# DC-DC_VCC_IN__3V.net
KiCad netlist of a schematic drawn in Altium Designer
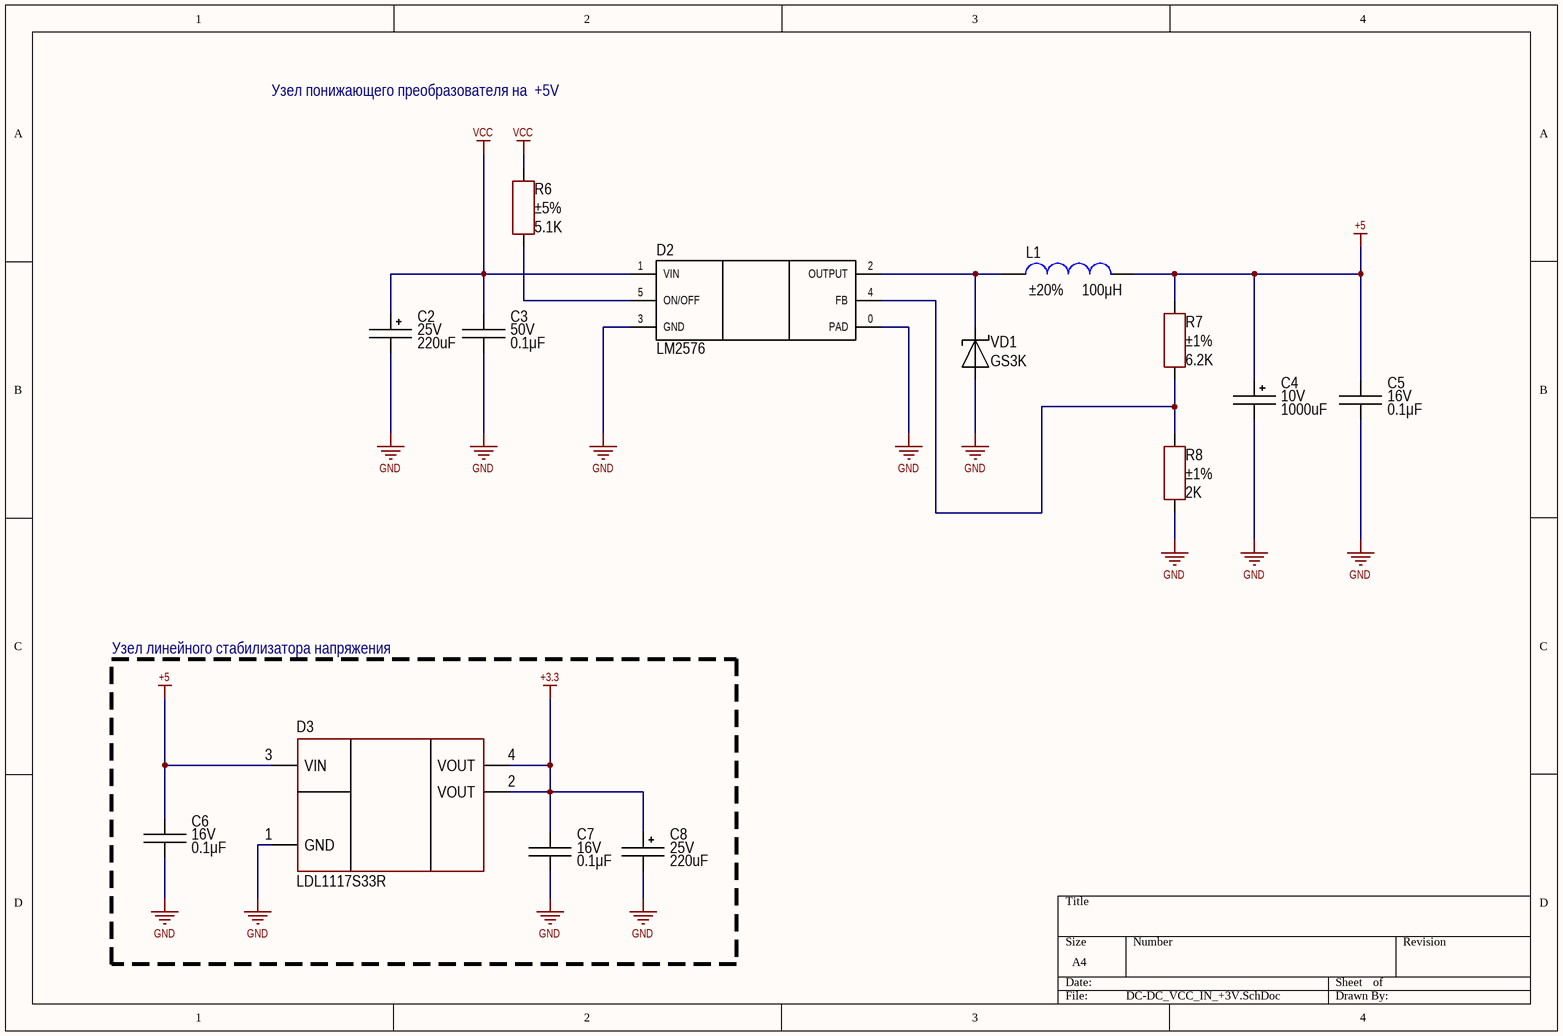
[diagram p0: DC-DC_VCC_IN_+3V.SchDoc]

(export (version "E")
  (design (tool "Eeschema 10.0.6"))
  (components
    (comp (ref "C2")
      (value "220uF")
      (footprint "CAP: D6.3C2.5H11")
      (fields
        (field (name "MANUFACTURER") "Aishi")
        (field (name "PARTNUMBER") "42330")
        (field (name "VALUEMANUFACTURERPARTNUMBER") "Aluminium capacitor, 220uF, 25V, ±20%, 54mOhm, 6.3x12, -55...+105°C")
        (field (name "VOLTAGE") "25V")
      )
      (libsource (lib "capacitor") (part "Aluminium"))
    )
    (comp (ref "C3")
      (value "0.1μF")
      (footprint "CAP: 0603")
      (fields
        (field (name "MANUFACTURER") "Yageo")
        (field (name "PARTNUMBER") "CC0603KRX7R7BB104")
        (field (name "VALUEMANUFACTURERPARTNUMBER") "Ceramic capacitor, 0.1μF, X7R, ±10%, 50V, 0603, -55...+125°C")
        (field (name "VOLTAGE") "50V")
      )
      (libsource (lib "capacitor") (part "Ceramic_0603"))
    )
    (comp (ref "C4")
      (value "1000uF")
      (footprint "CAP: D8C3.5H12")
      (fields
        (field (name "MANUFACTURER") "Aishi")
        (field (name "PARTNUMBER") "01675")
        (field (name "VALUEMANUFACTURERPARTNUMBER") "Aluminium capacitor, 1000uF, 10V, ±20%, 54mOhm, 8x12, -55...+105°C")
        (field (name "VOLTAGE") "10V")
      )
      (libsource (lib "capacitor") (part "Aluminium"))
    )
    (comp (ref "C5")
      (value "0.1μF")
      (footprint "CAP: 0603")
      (fields
        (field (name "MANUFACTURER") "Yageo")
        (field (name "PARTNUMBER") "CC0603KRX7R7BB104")
        (field (name "VALUEMANUFACTURERPARTNUMBER") "Ceramic capacitor, 0.1μF, X7R, ±10%, 16V, 0603, -55...+125°C")
        (field (name "VOLTAGE") "16V")
      )
      (libsource (lib "capacitor") (part "Ceramic_0603"))
    )
    (comp (ref "C6")
      (value "0.1μF")
      (footprint "CAP: 0603")
      (fields
        (field (name "MANUFACTURER") "Yageo")
        (field (name "PARTNUMBER") "CC0603KRX7R7BB104")
        (field (name "VALUEMANUFACTURERPARTNUMBER") "Ceramic capacitor, 0.1μF, X7R, ±10%, 16V, 0603, -55...+125°C")
        (field (name "VOLTAGE") "16V")
      )
      (libsource (lib "capacitor") (part "Ceramic_0603"))
    )
    (comp (ref "C7")
      (value "0.1μF")
      (footprint "CAP: 0603")
      (fields
        (field (name "MANUFACTURER") "Yageo")
        (field (name "PARTNUMBER") "CC0603KRX7R7BB104")
        (field (name "VALUEMANUFACTURERPARTNUMBER") "Ceramic capacitor, 0.1μF, X7R, ±10%, 16V, 0603, -55...+125°C")
        (field (name "VOLTAGE") "16V")
      )
      (libsource (lib "capacitor") (part "Ceramic_0603"))
    )
    (comp (ref "C8")
      (value "220uF")
      (footprint "CAP: D6.3C2.5H11")
      (fields
        (field (name "MANUFACTURER") "Aishi")
        (field (name "PARTNUMBER") "42330")
        (field (name "VALUEMANUFACTURERPARTNUMBER") "Aluminium capacitor, 220uF, 25V, ±20%, 54mOhm, 6.3x12, -55...+105°C")
        (field (name "VOLTAGE") "25V")
      )
      (libsource (lib "capacitor") (part "Aluminium"))
    )
    (comp (ref "D2")
      (value "~")
      (footprint "TO-220-5")
      (description "Step-Down Voltage Regulator")
      (fields
        (field (name "MANUFACTURER") "texas instruments")
        (field (name "VALUEMANUFACTURERPARTNUMBER") "Step-Down Voltage Regulator, 7-40V, 52kHz, 1.23V to 37V, 3A, -40...+125°C, TO-220")
        (field (name "PARTNUMBER") "LM2576")
      )
      (libsource (lib "ic-power-supply") (part "LM2576"))
    )
    (comp (ref "D3")
      (value "~")
      (footprint "SOT223")
      (description "Linear voltage regulator")
      (fields
        (field (name "MANUFACTURER") "STMicroelectronics")
        (field (name "VALUEMANUFACTURERPARTNUMBER") "Linear voltage regulator, input 3.9...18V, 0.6V, output 3.3V, 1.2A, -40...+85°C, SOT223")
        (field (name "PARTNUMBER") "LDL1117S33R")
      )
      (libsource (lib "ic-power-supply") (part "LDL1117S33R"))
    )
    (comp (ref "L1")
      (value "100μH")
      (footprint "CDRH")
      (fields
        (field (name "MANUFACTURER") "Bourns")
        (field (name "PARTNUMBER") "CDRH")
        (field (name "VALUEMANUFACTURERPARTNUMBER") "Fixed inductor, 100μH, ±20%, CDRH101R, 3A, -40...+150°C")
        (field (name "TOLERANCE") "±20%")
      )
      (libsource (lib "inductor") (part "Inductor_CDRH"))
    )
    (comp (ref "R6")
      (value "5.1K")
      (footprint "RES: 0603")
      (fields
        (field (name "MANUFACTURER") "Yageo")
        (field (name "PARTNUMBER") "RC0603JR-07100RL")
        (field (name "VALUEMANUFACTURERPARTNUMBER") "Resistor film, 5.1K, ±5%, 0603, 0.1W, -55...+125°C")
        (field (name "TOLERANCE") "±5%")
      )
      (libsource (lib "resistor") (part "Resistor_0603"))
    )
    (comp (ref "R7")
      (value "6.2K")
      (footprint "RES: 0603")
      (fields
        (field (name "MANUFACTURER") "Yageo")
        (field (name "PARTNUMBER") "RC0603JR-07100RL")
        (field (name "VALUEMANUFACTURERPARTNUMBER") "Resistor film, 6.2K, ±1%, 0603, 0.1W, -55...+125°C")
        (field (name "TOLERANCE") "±1%")
      )
      (libsource (lib "resistor") (part "Resistor_0603"))
    )
    (comp (ref "R8")
      (value "2K")
      (footprint "RES: 0603")
      (fields
        (field (name "MANUFACTURER") "Yageo")
        (field (name "PARTNUMBER") "RC0603JR-07100RL")
        (field (name "VALUEMANUFACTURERPARTNUMBER") "Resistor film, 2K, ±1%, 0603, 0.1W, -55...+125°C")
        (field (name "TOLERANCE") "±1%")
      )
      (libsource (lib "resistor") (part "Resistor_0603"))
    )
    (comp (ref "VD1")
      (value "~")
      (footprint "DIODE: SMC")
      (fields
        (field (name "MANUFACTURER") "Yangzhou Yangjie Electronic Technology Co., Ltd.")
        (field (name "VALUEMANUFACTURERPARTNUMBER") "Schottky diode, 800V, 3A, 1.15V, 15pF, DO-214AB / SMC, -55...+150°C")
        (field (name "VOLTAGE") "800V")
        (field (name "PARTNUMBER") "GS3K")
      )
      (libsource (lib "diode") (part "Schottky_single"))
    )
  )
  (nets
    (net (code "1") (name "+3.3") (class "Default")
      (node (ref "C7") (pin "2") (pinfunction "2_2") (pintype "passive"))
      (node (ref "C8") (pin "1") (pinfunction "1_1") (pintype "passive"))
      (node (ref "D3") (pin "2") (pinfunction "VOUT_2") (pintype "power_in"))
      (node (ref "D3") (pin "4") (pinfunction "VOUT_4") (pintype "power_in"))
    )
    (net (code "2") (name "+5") (class "Default")
      (node (ref "C4") (pin "1") (pinfunction "1_1") (pintype "passive"))
      (node (ref "C5") (pin "2") (pinfunction "2_2") (pintype "passive"))
      (node (ref "C6") (pin "2") (pinfunction "2_2") (pintype "passive"))
      (node (ref "D3") (pin "3") (pinfunction "VIN_3") (pintype "power_in"))
      (node (ref "L1") (pin "1") (pinfunction "1_1") (pintype "passive"))
      (node (ref "R7") (pin "2") (pinfunction "2_2") (pintype "passive"))
    )
    (net (code "3") (name "GND") (class "Default")
      (node (ref "C2") (pin "2") (pinfunction "2_2") (pintype "passive"))
      (node (ref "C3") (pin "1") (pinfunction "1_1") (pintype "passive"))
      (node (ref "C4") (pin "2") (pinfunction "2_2") (pintype "passive"))
      (node (ref "C5") (pin "1") (pinfunction "1_1") (pintype "passive"))
      (node (ref "C6") (pin "1") (pinfunction "1_1") (pintype "passive"))
      (node (ref "C7") (pin "1") (pinfunction "1_1") (pintype "passive"))
      (node (ref "C8") (pin "2") (pinfunction "2_2") (pintype "passive"))
      (node (ref "D2") (pin "0") (pinfunction "PAD_0") (pintype "passive"))
      (node (ref "D2") (pin "3") (pinfunction "GND_3") (pintype "passive"))
      (node (ref "D3") (pin "1") (pinfunction "GND_1") (pintype "power_in"))
      (node (ref "R8") (pin "1") (pinfunction "1_1") (pintype "passive"))
      (node (ref "VD1") (pin "1") (pinfunction "1_1") (pintype "passive"))
    )
    (net (code "4") (name "Net-(D2-FB)") (class "Default")
      (node (ref "D2") (pin "4") (pinfunction "FB_4") (pintype "passive"))
      (node (ref "R7") (pin "1") (pinfunction "1_1") (pintype "passive"))
      (node (ref "R8") (pin "2") (pinfunction "2_2") (pintype "passive"))
    )
    (net (code "5") (name "Net-(D2-ON{slash}OFF)") (class "Default")
      (node (ref "D2") (pin "5") (pinfunction "ON/OFF_5") (pintype "passive"))
      (node (ref "R6") (pin "1") (pinfunction "1_1") (pintype "passive"))
    )
    (net (code "6") (name "Net-(D2-OUTPUT)") (class "Default")
      (node (ref "D2") (pin "2") (pinfunction "OUTPUT_2") (pintype "passive"))
      (node (ref "L1") (pin "2") (pinfunction "2_2") (pintype "passive"))
      (node (ref "VD1") (pin "2") (pinfunction "2_2") (pintype "passive"))
    )
    (net (code "7") (name "VCC") (class "Default")
      (node (ref "C2") (pin "1") (pinfunction "1_1") (pintype "passive"))
      (node (ref "C3") (pin "2") (pinfunction "2_2") (pintype "passive"))
      (node (ref "D2") (pin "1") (pinfunction "VIN_1") (pintype "passive"))
      (node (ref "R6") (pin "2") (pinfunction "2_2") (pintype "passive"))
    )
  )
)
